# buttons.net
KiCad netlist of a schematic drawn in EAGLE
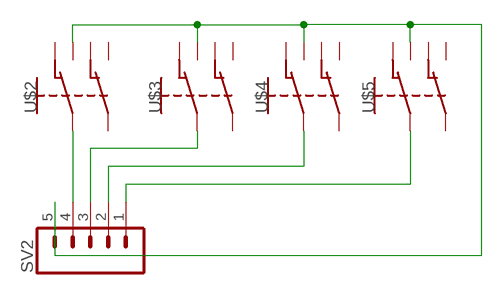
[diagram p0: schematic, sheet 1]

(export (version "E")
  (design (tool "Eeschema 10.0.6"))
  (components
    (comp (ref "SV2")
      (value "CONN_05")
      (footprint "eagle-import:1X05")
      (libsource (lib "eagle-import") (part "CONN_05"))
    )
    (comp (ref "U$2")
      (value "PVA2-OA")
      (footprint "eagle-import:PVA")
      (libsource (lib "eagle-import") (part "PVA2-OA"))
    )
    (comp (ref "U$3")
      (value "PVA2-OA")
      (footprint "eagle-import:PVA")
      (libsource (lib "eagle-import") (part "PVA2-OA"))
    )
    (comp (ref "U$4")
      (value "PVA2-OA")
      (footprint "eagle-import:PVA")
      (libsource (lib "eagle-import") (part "PVA2-OA"))
    )
    (comp (ref "U$5")
      (value "PVA2-OA")
      (footprint "eagle-import:PVA")
      (libsource (lib "eagle-import") (part "PVA2-OA"))
    )
  )
  (nets
    (net (code "1") (name "Net-(SV2-Pad1)") (class "Default")
      (node (ref "SV2") (pin "1") (pinfunction "1_1") (pintype "passive"))
      (node (ref "U$5") (pin "0") (pinfunction "0_0") (pintype "passive"))
    )
    (net (code "2") (name "Net-(SV2-Pad2)") (class "Default")
      (node (ref "SV2") (pin "2") (pinfunction "2_2") (pintype "passive"))
      (node (ref "U$4") (pin "0") (pinfunction "0_0") (pintype "passive"))
    )
    (net (code "3") (name "Net-(SV2-Pad3)") (class "Default")
      (node (ref "SV2") (pin "3") (pinfunction "3_3") (pintype "passive"))
      (node (ref "U$3") (pin "0") (pinfunction "0_0") (pintype "passive"))
    )
    (net (code "4") (name "Net-(SV2-Pad4)") (class "Default")
      (node (ref "SV2") (pin "4") (pinfunction "4_4") (pintype "passive"))
      (node (ref "U$2") (pin "0") (pinfunction "0_0") (pintype "passive"))
    )
    (net (code "5") (name "Net-(SV2-Pad5)") (class "Default")
      (node (ref "SV2") (pin "5") (pinfunction "5_5") (pintype "passive"))
      (node (ref "U$2") (pin "2") (pinfunction "2_2") (pintype "passive"))
      (node (ref "U$3") (pin "2") (pinfunction "2_2") (pintype "passive"))
      (node (ref "U$4") (pin "2") (pinfunction "2_2") (pintype "passive"))
      (node (ref "U$5") (pin "2") (pinfunction "2_2") (pintype "passive"))
    )
    (net (code "6") (name "unconnected-(U$2-Pad0')") (class "Default")
      (node (ref "U$2") (pin "0'") (pinfunction "0'_0'") (pintype "passive"))
    )
    (net (code "7") (name "unconnected-(U$2-Pad1')") (class "Default")
      (node (ref "U$2") (pin "1'") (pinfunction "1'_1'") (pintype "passive"))
    )
    (net (code "8") (name "unconnected-(U$2-Pad1)") (class "Default")
      (node (ref "U$2") (pin "1") (pinfunction "1_1") (pintype "passive"))
    )
    (net (code "9") (name "unconnected-(U$2-Pad2')") (class "Default")
      (node (ref "U$2") (pin "2'") (pinfunction "2'_2'") (pintype "passive"))
    )
    (net (code "10") (name "unconnected-(U$3-Pad0')") (class "Default")
      (node (ref "U$3") (pin "0'") (pinfunction "0'_0'") (pintype "passive"))
    )
    (net (code "11") (name "unconnected-(U$3-Pad1')") (class "Default")
      (node (ref "U$3") (pin "1'") (pinfunction "1'_1'") (pintype "passive"))
    )
    (net (code "12") (name "unconnected-(U$3-Pad1)") (class "Default")
      (node (ref "U$3") (pin "1") (pinfunction "1_1") (pintype "passive"))
    )
    (net (code "13") (name "unconnected-(U$3-Pad2')") (class "Default")
      (node (ref "U$3") (pin "2'") (pinfunction "2'_2'") (pintype "passive"))
    )
    (net (code "14") (name "unconnected-(U$4-Pad0')") (class "Default")
      (node (ref "U$4") (pin "0'") (pinfunction "0'_0'") (pintype "passive"))
    )
    (net (code "15") (name "unconnected-(U$4-Pad1')") (class "Default")
      (node (ref "U$4") (pin "1'") (pinfunction "1'_1'") (pintype "passive"))
    )
    (net (code "16") (name "unconnected-(U$4-Pad1)") (class "Default")
      (node (ref "U$4") (pin "1") (pinfunction "1_1") (pintype "passive"))
    )
    (net (code "17") (name "unconnected-(U$4-Pad2')") (class "Default")
      (node (ref "U$4") (pin "2'") (pinfunction "2'_2'") (pintype "passive"))
    )
    (net (code "18") (name "unconnected-(U$5-Pad0')") (class "Default")
      (node (ref "U$5") (pin "0'") (pinfunction "0'_0'") (pintype "passive"))
    )
    (net (code "19") (name "unconnected-(U$5-Pad1')") (class "Default")
      (node (ref "U$5") (pin "1'") (pinfunction "1'_1'") (pintype "passive"))
    )
    (net (code "20") (name "unconnected-(U$5-Pad1)") (class "Default")
      (node (ref "U$5") (pin "1") (pinfunction "1_1") (pintype "passive"))
    )
    (net (code "21") (name "unconnected-(U$5-Pad2')") (class "Default")
      (node (ref "U$5") (pin "2'") (pinfunction "2'_2'") (pintype "passive"))
    )
  )
)
